# bp2ng.net
KiCad netlist of a schematic drawn in EAGLE
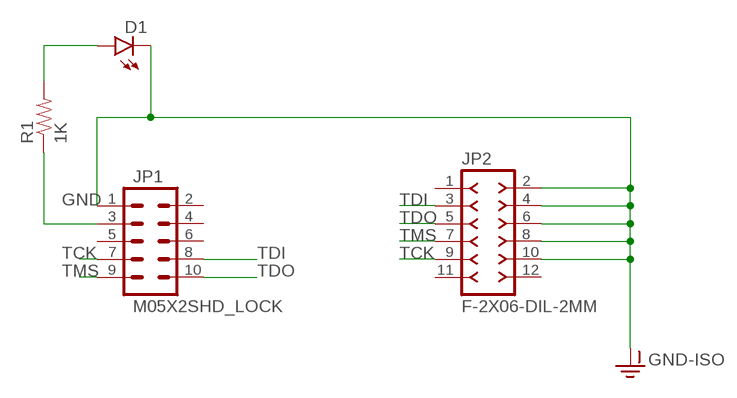
[diagram p0: schematic, sheet 1]

(export (version "E")
  (design (tool "Eeschema 10.0.6"))
  (components
    (comp (ref "D1")
      (value "LED1206")
      (footprint "eagle-import:LED-1206")
      (libsource (lib "eagle-import") (part "LED1206"))
    )
    (comp (ref "JP1")
      (value "M05X2SHD_LOCK")
      (footprint "eagle-import:2X5-SHROUDED_LOCK")
      (libsource (lib "eagle-import") (part "M05X2SHD_LOCK"))
    )
    (comp (ref "JP2")
      (value "F-2X06-DIL-2MM")
      (footprint "eagle-import:DIL-2MM-2X06")
      (libsource (lib "eagle-import") (part "F-2X06-DIL-2MM"))
    )
    (comp (ref "R1")
      (value "1K")
      (footprint "eagle-import:1206")
      (libsource (lib "eagle-import") (part "RESISTOR1206"))
    )
  )
  (nets
    (net (code "1") (name "/TCK") (class "Default")
      (node (ref "JP1") (pin "7") (pinfunction "7_7") (pintype "passive"))
      (node (ref "JP2") (pin "9") (pinfunction "9_9") (pintype "passive"))
    )
    (net (code "2") (name "/TDI") (class "Default")
      (node (ref "JP1") (pin "8") (pinfunction "8_8") (pintype "passive"))
      (node (ref "JP2") (pin "3") (pinfunction "3_3") (pintype "passive"))
    )
    (net (code "3") (name "/TDO") (class "Default")
      (node (ref "JP1") (pin "10") (pinfunction "10_10") (pintype "passive"))
      (node (ref "JP2") (pin "5") (pinfunction "5_5") (pintype "passive"))
    )
    (net (code "4") (name "/TMS") (class "Default")
      (node (ref "JP1") (pin "9") (pinfunction "9_9") (pintype "passive"))
      (node (ref "JP2") (pin "7") (pinfunction "7_7") (pintype "passive"))
    )
    (net (code "5") (name "GND-ISO") (class "Default")
      (node (ref "D1") (pin "C") (pinfunction "C_C") (pintype "passive"))
      (node (ref "JP1") (pin "1") (pinfunction "1_1") (pintype "passive"))
      (node (ref "JP2") (pin "10") (pinfunction "10_10") (pintype "passive"))
      (node (ref "JP2") (pin "2") (pinfunction "2_2") (pintype "passive"))
      (node (ref "JP2") (pin "4") (pinfunction "4_4") (pintype "passive"))
      (node (ref "JP2") (pin "6") (pinfunction "6_6") (pintype "passive"))
      (node (ref "JP2") (pin "8") (pinfunction "8_8") (pintype "passive"))
    )
    (net (code "6") (name "Net-(D1-PadA)") (class "Default")
      (node (ref "D1") (pin "A") (pinfunction "A_A") (pintype "passive"))
      (node (ref "R1") (pin "2") (pinfunction "2_2") (pintype "passive"))
    )
    (net (code "7") (name "Net-(JP1-Pad3)") (class "Default")
      (node (ref "JP1") (pin "3") (pinfunction "3_3") (pintype "passive"))
      (node (ref "R1") (pin "1") (pinfunction "1_1") (pintype "passive"))
    )
    (net (code "8") (name "unconnected-(JP1-Pad2)") (class "Default")
      (node (ref "JP1") (pin "2") (pinfunction "2_2") (pintype "passive"))
    )
    (net (code "9") (name "unconnected-(JP1-Pad4)") (class "Default")
      (node (ref "JP1") (pin "4") (pinfunction "4_4") (pintype "passive"))
    )
    (net (code "10") (name "unconnected-(JP1-Pad5)") (class "Default")
      (node (ref "JP1") (pin "5") (pinfunction "5_5") (pintype "passive"))
    )
    (net (code "11") (name "unconnected-(JP1-Pad6)") (class "Default")
      (node (ref "JP1") (pin "6") (pinfunction "6_6") (pintype "passive"))
    )
    (net (code "12") (name "unconnected-(JP2-Pad1)") (class "Default")
      (node (ref "JP2") (pin "1") (pinfunction "1_1") (pintype "passive"))
    )
    (net (code "13") (name "unconnected-(JP2-Pad11)") (class "Default")
      (node (ref "JP2") (pin "11") (pinfunction "11_11") (pintype "passive"))
    )
    (net (code "14") (name "unconnected-(JP2-Pad12)") (class "Default")
      (node (ref "JP2") (pin "12") (pinfunction "12_12") (pintype "passive"))
    )
  )
)
